# HAT.net
KiCad netlist of a schematic drawn in Altium Designer
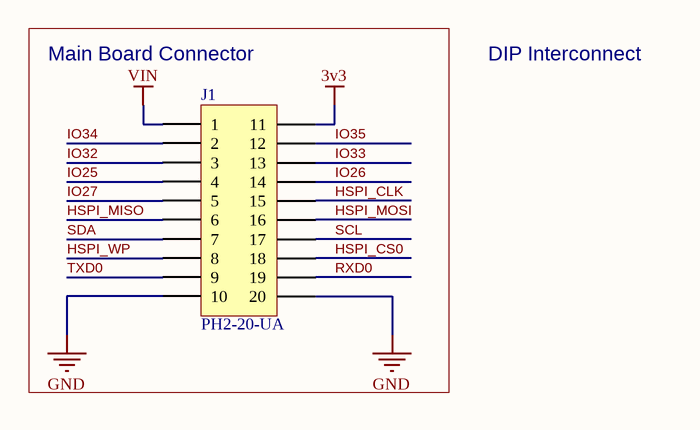
[diagram p0: HAT.SchDoc]

(export (version "E")
  (design (tool "Eeschema 10.0.6"))
  (components
    (comp (ref "J1")
      (value "PH2-20-UA")
      (footprint "PH2-20-UA-BottomFootprint")
      (description "Male Header 2 x 10 - 2.54mm Pitch")
      (libsource (lib "RIT Launch Initiative") (part "PH2-20-UA"))
    )
  )
  (nets
    (net (code "1") (name "/HSPI_CLK") (class "Default")
      (node (ref "J1") (pin "15") (pinfunction "15_15") (pintype "passive"))
    )
    (net (code "2") (name "/HSPI_CS0") (class "Default")
      (node (ref "J1") (pin "18") (pinfunction "18_18") (pintype "passive"))
    )
    (net (code "3") (name "/HSPI_MISO") (class "Default")
      (node (ref "J1") (pin "6") (pinfunction "6_6") (pintype "passive"))
    )
    (net (code "4") (name "/HSPI_MOSI") (class "Default")
      (node (ref "J1") (pin "16") (pinfunction "16_16") (pintype "passive"))
    )
    (net (code "5") (name "/HSPI_WP") (class "Default")
      (node (ref "J1") (pin "8") (pinfunction "8_8") (pintype "passive"))
    )
    (net (code "6") (name "/IO25") (class "Default")
      (node (ref "J1") (pin "4") (pinfunction "4_4") (pintype "passive"))
    )
    (net (code "7") (name "/IO26") (class "Default")
      (node (ref "J1") (pin "14") (pinfunction "14_14") (pintype "passive"))
    )
    (net (code "8") (name "/IO27") (class "Default")
      (node (ref "J1") (pin "5") (pinfunction "5_5") (pintype "passive"))
    )
    (net (code "9") (name "/IO32") (class "Default")
      (node (ref "J1") (pin "3") (pinfunction "3_3") (pintype "passive"))
    )
    (net (code "10") (name "/IO33") (class "Default")
      (node (ref "J1") (pin "13") (pinfunction "13_13") (pintype "passive"))
    )
    (net (code "11") (name "/IO34") (class "Default")
      (node (ref "J1") (pin "2") (pinfunction "2_2") (pintype "passive"))
    )
    (net (code "12") (name "/IO35") (class "Default")
      (node (ref "J1") (pin "12") (pinfunction "12_12") (pintype "passive"))
    )
    (net (code "13") (name "/RXD0") (class "Default")
      (node (ref "J1") (pin "19") (pinfunction "19_19") (pintype "passive"))
    )
    (net (code "14") (name "/SCL") (class "Default")
      (node (ref "J1") (pin "17") (pinfunction "17_17") (pintype "passive"))
    )
    (net (code "15") (name "/SDA") (class "Default")
      (node (ref "J1") (pin "7") (pinfunction "7_7") (pintype "passive"))
    )
    (net (code "16") (name "/TXD0") (class "Default")
      (node (ref "J1") (pin "9") (pinfunction "9_9") (pintype "passive"))
    )
    (net (code "17") (name "3v3") (class "Default")
      (node (ref "J1") (pin "11") (pinfunction "11_11") (pintype "passive"))
    )
    (net (code "18") (name "GND") (class "Default")
      (node (ref "J1") (pin "10") (pinfunction "10_10") (pintype "passive"))
      (node (ref "J1") (pin "20") (pinfunction "20_20") (pintype "passive"))
    )
    (net (code "19") (name "VIN") (class "Default")
      (node (ref "J1") (pin "1") (pinfunction "1_1") (pintype "passive"))
    )
  )
)
